# RotaryEncoder.net
KiCad netlist of a schematic drawn in EAGLE
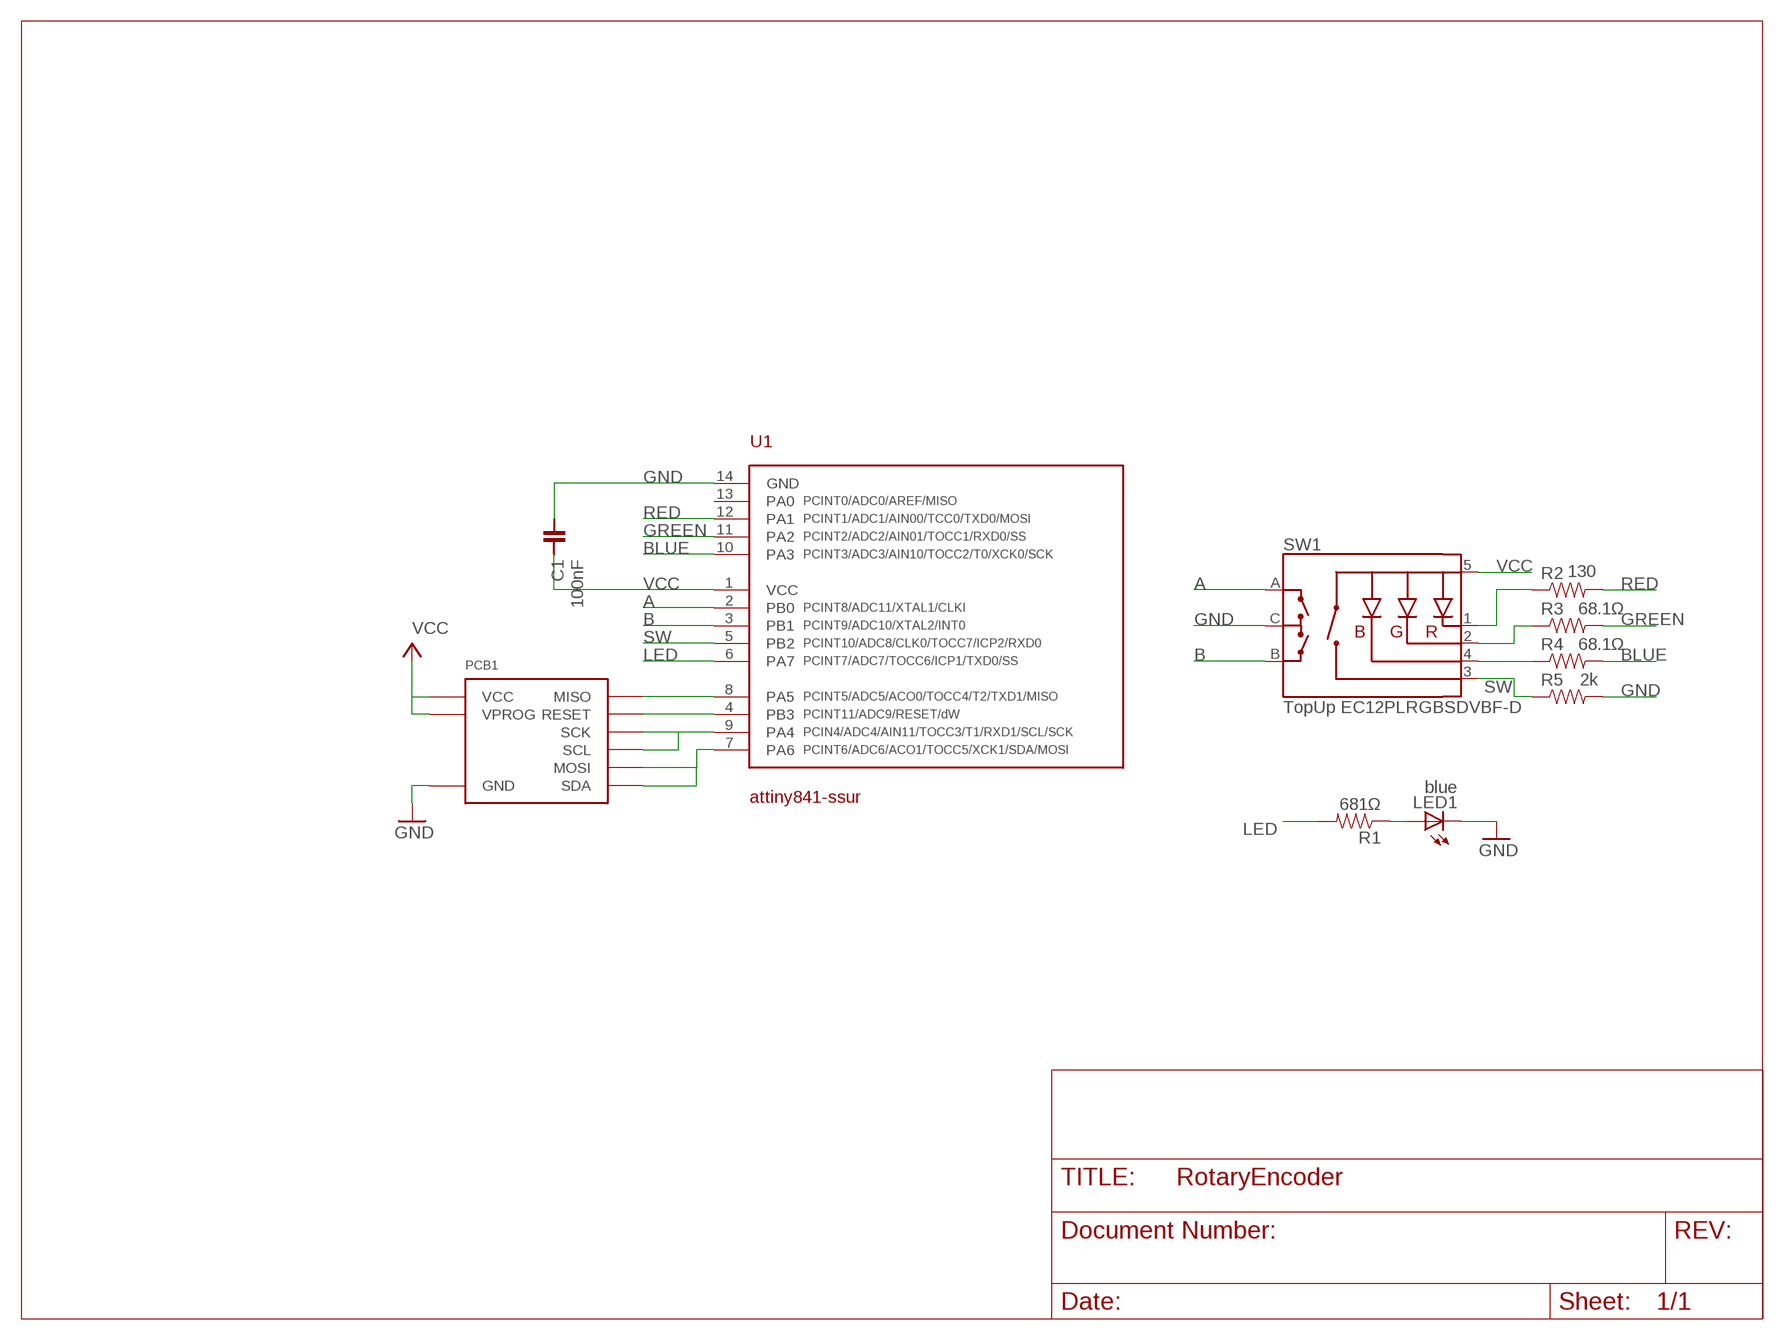
[diagram p0: schematic, sheet 1]

(export (version "E")
  (design (tool "Eeschema 10.0.6"))
  (components
    (comp (ref "C1")
      (value "100nF")
      (footprint "eagle-import:0603")
      (fields (field (name "PARTNUM") "C0603C104K5RACTU"))
      (libsource (lib "eagle-import") (part "CAPACITOR-100NF"))
    )
    (comp (ref "LED1")
      (value "blue")
      (footprint "eagle-import:0805-LED")
      (fields (field (name "PARTNUM") "LTST-C171TBKT"))
      (libsource (lib "eagle-import") (part "LED-0805-BLUE"))
    )
    (comp (ref "PCB1")
      (value "DEVICE-PCB-TABS")
      (footprint "eagle-import:DEVICE-PCB-TABS")
      (libsource (lib "eagle-import") (part "DEVICE-PCB-TABS"))
    )
    (comp (ref "R1")
      (value "681Ω")
      (footprint "eagle-import:0603")
      (fields (field (name "PARTNUM") "ERJ-3EKF6810V"))
      (libsource (lib "eagle-import") (part "RESISTOR-681Ω"))
    )
    (comp (ref "R2")
      (value "130")
      (footprint "eagle-import:0603")
      (libsource (lib "eagle-import") (part "RESISTOR-0603"))
    )
    (comp (ref "R3")
      (value "68.1Ω")
      (footprint "eagle-import:0603")
      (fields (field (name "PARTNUM") "ERJ-3EKF68R1V"))
      (libsource (lib "eagle-import") (part "RESISTOR-68.1Ω"))
    )
    (comp (ref "R4")
      (value "68.1Ω")
      (footprint "eagle-import:0603")
      (fields (field (name "PARTNUM") "ERJ-3EKF68R1V"))
      (libsource (lib "eagle-import") (part "RESISTOR-68.1Ω"))
    )
    (comp (ref "R5")
      (value "2k")
      (footprint "eagle-import:0603")
      (libsource (lib "eagle-import") (part "RESISTOR-0603"))
    )
    (comp (ref "SW1")
      (value "TopUp EC12PLRGBSDVBF-D")
      (footprint "eagle-import:ENCODER_LED_3")
      (libsource (lib "eagle-import") (part "ENCODER_RGB_CA"))
    )
    (comp (ref "U1")
      (value "attiny841-ssur")
      (footprint "eagle-import:SOIC14")
      (libsource (lib "eagle-import") (part "ATTINY841"))
    )
  )
  (nets
    (net (code "1") (name "/A") (class "Default")
      (node (ref "SW1") (pin "A") (pinfunction "A_A") (pintype "bidirectional"))
      (node (ref "U1") (pin "2") (pinfunction "PB0_2") (pintype "bidirectional"))
    )
    (net (code "2") (name "/B") (class "Default")
      (node (ref "SW1") (pin "B") (pinfunction "B_B") (pintype "bidirectional"))
      (node (ref "U1") (pin "3") (pinfunction "PB1_3") (pintype "bidirectional"))
    )
    (net (code "3") (name "/BLUE") (class "Default")
      (node (ref "R4") (pin "2") (pinfunction "2_2") (pintype "passive"))
      (node (ref "U1") (pin "10") (pinfunction "PA3_10") (pintype "bidirectional"))
    )
    (net (code "4") (name "/GREEN") (class "Default")
      (node (ref "R3") (pin "2") (pinfunction "2_2") (pintype "passive"))
      (node (ref "U1") (pin "11") (pinfunction "PA2_11") (pintype "bidirectional"))
    )
    (net (code "5") (name "/LED") (class "Default")
      (node (ref "R1") (pin "2") (pinfunction "2_2") (pintype "passive"))
      (node (ref "U1") (pin "6") (pinfunction "PA7_6") (pintype "bidirectional"))
    )
    (net (code "6") (name "/RED") (class "Default")
      (node (ref "R2") (pin "2") (pinfunction "2_2") (pintype "passive"))
      (node (ref "U1") (pin "12") (pinfunction "PA1_12") (pintype "bidirectional"))
    )
    (net (code "7") (name "/SW") (class "Default")
      (node (ref "R5") (pin "1") (pinfunction "1_1") (pintype "passive"))
      (node (ref "SW1") (pin "3") (pinfunction "SW_3") (pintype "passive"))
      (node (ref "U1") (pin "5") (pinfunction "PB2_5") (pintype "bidirectional"))
    )
    (net (code "8") (name "GND") (class "Default")
      (node (ref "C1") (pin "2") (pinfunction "2_2") (pintype "passive"))
      (node (ref "LED1") (pin "C") (pinfunction "C_C") (pintype "passive"))
      (node (ref "PCB1") (pin "BUS0") (pinfunction "GND_BUS0") (pintype "bidirectional"))
      (node (ref "R5") (pin "2") (pinfunction "2_2") (pintype "passive"))
      (node (ref "SW1") (pin "C") (pinfunction "C_C") (pintype "bidirectional"))
      (node (ref "U1") (pin "14") (pinfunction "GND_14") (pintype "bidirectional"))
    )
    (net (code "9") (name "Net-(LED1-PadA)") (class "Default")
      (node (ref "LED1") (pin "A") (pinfunction "A_A") (pintype "passive"))
      (node (ref "R1") (pin "1") (pinfunction "1_1") (pintype "passive"))
    )
    (net (code "10") (name "Net-(PCB1-MISO)") (class "Default")
      (node (ref "PCB1") (pin "PROG3") (pinfunction "MISO_PROG3") (pintype "bidirectional"))
      (node (ref "U1") (pin "8") (pinfunction "PA5_8") (pintype "bidirectional"))
    )
    (net (code "11") (name "Net-(PCB1-MOSI)") (class "Default")
      (node (ref "PCB1") (pin "BUS1") (pinfunction "SDA_BUS1") (pintype "bidirectional"))
      (node (ref "PCB1") (pin "PROG4") (pinfunction "MOSI_PROG4") (pintype "bidirectional"))
      (node (ref "U1") (pin "7") (pinfunction "PA6_7") (pintype "bidirectional"))
    )
    (net (code "12") (name "Net-(PCB1-RESET)") (class "Default")
      (node (ref "PCB1") (pin "PROG1") (pinfunction "RESET_PROG1") (pintype "bidirectional"))
      (node (ref "U1") (pin "4") (pinfunction "PB3_4") (pintype "bidirectional"))
    )
    (net (code "13") (name "Net-(PCB1-SCK)") (class "Default")
      (node (ref "PCB1") (pin "BUS3") (pinfunction "SCL_BUS3") (pintype "bidirectional"))
      (node (ref "PCB1") (pin "PROG2") (pinfunction "SCK_PROG2") (pintype "bidirectional"))
      (node (ref "U1") (pin "9") (pinfunction "PA4_9") (pintype "bidirectional"))
    )
    (net (code "14") (name "Net-(SW1--B)") (class "Default")
      (node (ref "R4") (pin "1") (pinfunction "1_1") (pintype "passive"))
      (node (ref "SW1") (pin "4") (pinfunction "-B_4") (pintype "passive"))
    )
    (net (code "15") (name "Net-(SW1--G)") (class "Default")
      (node (ref "R3") (pin "1") (pinfunction "1_1") (pintype "passive"))
      (node (ref "SW1") (pin "2") (pinfunction "-G_2") (pintype "passive"))
    )
    (net (code "16") (name "Net-(SW1--R)") (class "Default")
      (node (ref "R2") (pin "1") (pinfunction "1_1") (pintype "passive"))
      (node (ref "SW1") (pin "1") (pinfunction "-R_1") (pintype "passive"))
    )
    (net (code "17") (name "VCC") (class "Default")
      (node (ref "C1") (pin "1") (pinfunction "1_1") (pintype "passive"))
      (node (ref "PCB1") (pin "BUS2") (pinfunction "VCC_BUS2") (pintype "bidirectional"))
      (node (ref "PCB1") (pin "PROG0") (pinfunction "VPROG_PROG0") (pintype "bidirectional"))
      (node (ref "SW1") (pin "5") (pinfunction "+_5") (pintype "passive"))
      (node (ref "U1") (pin "1") (pinfunction "VCC_1") (pintype "bidirectional"))
    )
    (net (code "18") (name "unconnected-(U1-PA0-Pad13)") (class "Default")
      (node (ref "U1") (pin "13") (pinfunction "PA0_13") (pintype "bidirectional"))
    )
  )
)
